# reset.net
KiCad netlist of a schematic drawn in Altium Designer
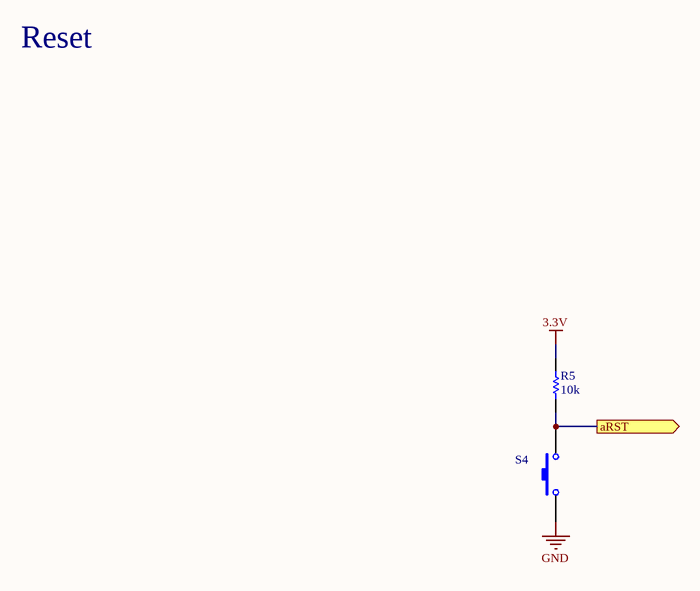
[diagram p0: reset.SchDoc]

(export (version "E")
  (design (tool "Eeschema 10.0.6"))
  (components
    (comp (ref "R5")
      (value "10k")
      (footprint "AXIAL-0.3")
      (description "Resistor")
      (fields (field (name "PUBLISHER") "Altium Limited"))
      (libsource (lib "Miscellaneous Devices") (part "Res1"))
    )
    (comp (ref "S4")
      (value "Switch")
      (footprint "SPST-2")
      (description "Reset")
      (fields (field (name "PUBLISHER") "Altium Limited"))
      (libsource (lib "Miscellaneous Devices") (part "SW-PB"))
    )
  )
  (nets
    (net (code "1") (name "/aRST") (class "Default")
      (node (ref "R5") (pin "1") (pinfunction "1_1") (pintype "passive"))
      (node (ref "S4") (pin "2") (pinfunction "2_2") (pintype "passive"))
    )
    (net (code "2") (name "3.3V") (class "Default")
      (node (ref "R5") (pin "2") (pinfunction "2_2") (pintype "passive"))
    )
    (net (code "3") (name "GND") (class "Default")
      (node (ref "S4") (pin "1") (pinfunction "1_1") (pintype "passive"))
    )
  )
)
